# pla_xc9536.net
KiCad netlist of a schematic drawn in EAGLE
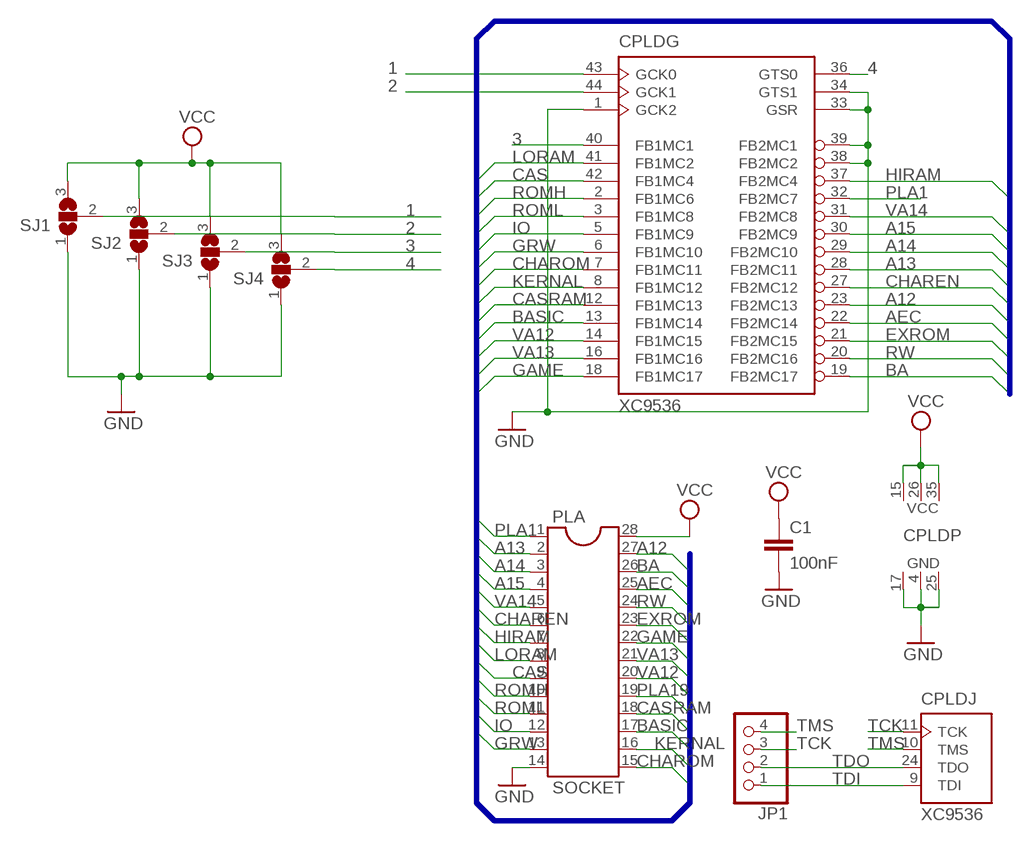
[diagram p0: schematic, sheet 1]

(export (version "E")
  (design (tool "Eeschema 10.0.6"))
  (components
    (comp (ref "C1")
      (value "100nF")
      (footprint "eagle-import:C1206K")
      (libsource (lib "eagle-import") (part "C-EUC1206K"))
    )
    (comp (ref "CPLD")
      (value "XC9536")
      (footprint "eagle-import:VQ44")
      (libsource (lib "eagle-import") (part "XC9536-44VQ44"))
    )
    (comp (ref "JP1")
      (value "PINHD-1X4")
      (footprint "eagle-import:1X04")
      (libsource (lib "eagle-import") (part "PINHD-1X4"))
    )
    (comp (ref "PLA")
      (value "SOCKET")
      (footprint "eagle-import:DIL28-6-ROUND")
      (libsource (lib "eagle-import") (part "DIL28"))
    )
    (comp (ref "SJ1")
      (value "SJ2W")
      (footprint "eagle-import:SJ_2")
      (libsource (lib "eagle-import") (part "SJ2W"))
    )
    (comp (ref "SJ2")
      (value "SJ2W")
      (footprint "eagle-import:SJ_2")
      (libsource (lib "eagle-import") (part "SJ2W"))
    )
    (comp (ref "SJ3")
      (value "SJ2W")
      (footprint "eagle-import:SJ_2")
      (libsource (lib "eagle-import") (part "SJ2W"))
    )
    (comp (ref "SJ4")
      (value "SJ2W")
      (footprint "eagle-import:SJ_2")
      (libsource (lib "eagle-import") (part "SJ2W"))
    )
  )
  (nets
    (net (code "1") (name "/1") (class "Default")
      (node (ref "CPLD") (pin "43") (pinfunction "GCK0_43") (pintype "input"))
      (node (ref "SJ1") (pin "2") (pinfunction "2_2") (pintype "passive"))
    )
    (net (code "2") (name "/2") (class "Default")
      (node (ref "CPLD") (pin "44") (pinfunction "GCK1_44") (pintype "input"))
      (node (ref "SJ2") (pin "2") (pinfunction "2_2") (pintype "passive"))
    )
    (net (code "3") (name "/3") (class "Default")
      (node (ref "CPLD") (pin "40") (pinfunction "FB1MC1_40") (pintype "bidirectional"))
      (node (ref "SJ3") (pin "2") (pinfunction "2_2") (pintype "passive"))
    )
    (net (code "4") (name "/4") (class "Default")
      (node (ref "CPLD") (pin "36") (pinfunction "GTS0_36") (pintype "input"))
      (node (ref "SJ4") (pin "2") (pinfunction "2_2") (pintype "passive"))
    )
    (net (code "5") (name "/A12") (class "Default")
      (node (ref "CPLD") (pin "23") (pinfunction "FB2MC13_23") (pintype "bidirectional"))
      (node (ref "PLA") (pin "27") (pinfunction "27_27") (pintype "passive"))
    )
    (net (code "6") (name "/A13") (class "Default")
      (node (ref "CPLD") (pin "28") (pinfunction "FB2MC11_28") (pintype "bidirectional"))
      (node (ref "PLA") (pin "2") (pinfunction "2_2") (pintype "passive"))
    )
    (net (code "7") (name "/A14") (class "Default")
      (node (ref "CPLD") (pin "29") (pinfunction "FB2MC10_29") (pintype "bidirectional"))
      (node (ref "PLA") (pin "3") (pinfunction "3_3") (pintype "passive"))
    )
    (net (code "8") (name "/A15") (class "Default")
      (node (ref "CPLD") (pin "30") (pinfunction "FB2MC9_30") (pintype "bidirectional"))
      (node (ref "PLA") (pin "4") (pinfunction "4_4") (pintype "passive"))
    )
    (net (code "9") (name "/AEC") (class "Default")
      (node (ref "CPLD") (pin "22") (pinfunction "FB2MC14_22") (pintype "bidirectional"))
      (node (ref "PLA") (pin "25") (pinfunction "25_25") (pintype "passive"))
    )
    (net (code "10") (name "/BA") (class "Default")
      (node (ref "CPLD") (pin "19") (pinfunction "FB2MC17_19") (pintype "bidirectional"))
      (node (ref "PLA") (pin "26") (pinfunction "26_26") (pintype "passive"))
    )
    (net (code "11") (name "/BASIC") (class "Default")
      (node (ref "CPLD") (pin "13") (pinfunction "FB1MC14_13") (pintype "bidirectional"))
      (node (ref "PLA") (pin "17") (pinfunction "17_17") (pintype "passive"))
    )
    (net (code "12") (name "/CAS") (class "Default")
      (node (ref "CPLD") (pin "42") (pinfunction "FB1MC4_42") (pintype "bidirectional"))
      (node (ref "PLA") (pin "9") (pinfunction "9_9") (pintype "passive"))
    )
    (net (code "13") (name "/CASRAM") (class "Default")
      (node (ref "CPLD") (pin "12") (pinfunction "FB1MC13_12") (pintype "bidirectional"))
      (node (ref "PLA") (pin "18") (pinfunction "18_18") (pintype "passive"))
    )
    (net (code "14") (name "/CHAREN") (class "Default")
      (node (ref "CPLD") (pin "27") (pinfunction "FB2MC12_27") (pintype "bidirectional"))
      (node (ref "PLA") (pin "6") (pinfunction "6_6") (pintype "passive"))
    )
    (net (code "15") (name "/CHAROM") (class "Default")
      (node (ref "CPLD") (pin "7") (pinfunction "FB1MC11_7") (pintype "bidirectional"))
      (node (ref "PLA") (pin "15") (pinfunction "15_15") (pintype "passive"))
    )
    (net (code "16") (name "/EXROM") (class "Default")
      (node (ref "CPLD") (pin "21") (pinfunction "FB2MC15_21") (pintype "bidirectional"))
      (node (ref "PLA") (pin "23") (pinfunction "23_23") (pintype "passive"))
    )
    (net (code "17") (name "/GAME") (class "Default")
      (node (ref "CPLD") (pin "18") (pinfunction "FB1MC17_18") (pintype "bidirectional"))
      (node (ref "PLA") (pin "22") (pinfunction "22_22") (pintype "passive"))
    )
    (net (code "18") (name "/GRW") (class "Default")
      (node (ref "CPLD") (pin "6") (pinfunction "FB1MC10_6") (pintype "bidirectional"))
      (node (ref "PLA") (pin "13") (pinfunction "13_13") (pintype "passive"))
    )
    (net (code "19") (name "/HIRAM") (class "Default")
      (node (ref "CPLD") (pin "37") (pinfunction "FB2MC4_37") (pintype "bidirectional"))
      (node (ref "PLA") (pin "7") (pinfunction "7_7") (pintype "passive"))
    )
    (net (code "20") (name "/IO") (class "Default")
      (node (ref "CPLD") (pin "5") (pinfunction "FB1MC9_5") (pintype "bidirectional"))
      (node (ref "PLA") (pin "12") (pinfunction "12_12") (pintype "passive"))
    )
    (net (code "21") (name "/KERNAL") (class "Default")
      (node (ref "CPLD") (pin "8") (pinfunction "FB1MC12_8") (pintype "bidirectional"))
      (node (ref "PLA") (pin "16") (pinfunction "16_16") (pintype "passive"))
    )
    (net (code "22") (name "/LORAM") (class "Default")
      (node (ref "CPLD") (pin "41") (pinfunction "FB1MC2_41") (pintype "bidirectional"))
      (node (ref "PLA") (pin "8") (pinfunction "8_8") (pintype "passive"))
    )
    (net (code "23") (name "/PLA1") (class "Default")
      (node (ref "CPLD") (pin "32") (pinfunction "FB2MC7_32") (pintype "bidirectional"))
      (node (ref "PLA") (pin "1") (pinfunction "1_1") (pintype "passive"))
    )
    (net (code "24") (name "/PLA19") (class "Default")
      (node (ref "PLA") (pin "19") (pinfunction "19_19") (pintype "passive"))
    )
    (net (code "25") (name "/ROMH") (class "Default")
      (node (ref "CPLD") (pin "2") (pinfunction "FB1MC6_2") (pintype "bidirectional"))
      (node (ref "PLA") (pin "10") (pinfunction "10_10") (pintype "passive"))
    )
    (net (code "26") (name "/ROML") (class "Default")
      (node (ref "CPLD") (pin "3") (pinfunction "FB1MC8_3") (pintype "bidirectional"))
      (node (ref "PLA") (pin "11") (pinfunction "11_11") (pintype "passive"))
    )
    (net (code "27") (name "/RW") (class "Default")
      (node (ref "CPLD") (pin "20") (pinfunction "FB2MC16_20") (pintype "bidirectional"))
      (node (ref "PLA") (pin "24") (pinfunction "24_24") (pintype "passive"))
    )
    (net (code "28") (name "/TCK") (class "Default")
      (node (ref "CPLD") (pin "11") (pinfunction "TCK_11") (pintype "input"))
      (node (ref "JP1") (pin "3") (pinfunction "3_3") (pintype "passive"))
    )
    (net (code "29") (name "/TDI") (class "Default")
      (node (ref "CPLD") (pin "9") (pinfunction "TDI_9") (pintype "input"))
      (node (ref "JP1") (pin "1") (pinfunction "1_1") (pintype "passive"))
    )
    (net (code "30") (name "/TDO") (class "Default")
      (node (ref "CPLD") (pin "24") (pinfunction "TDO_24") (pintype "output"))
      (node (ref "JP1") (pin "2") (pinfunction "2_2") (pintype "passive"))
    )
    (net (code "31") (name "/TMS") (class "Default")
      (node (ref "CPLD") (pin "10") (pinfunction "TMS_10") (pintype "input"))
      (node (ref "JP1") (pin "4") (pinfunction "4_4") (pintype "passive"))
    )
    (net (code "32") (name "/VA12") (class "Default")
      (node (ref "CPLD") (pin "14") (pinfunction "FB1MC15_14") (pintype "bidirectional"))
      (node (ref "PLA") (pin "20") (pinfunction "20_20") (pintype "passive"))
    )
    (net (code "33") (name "/VA13") (class "Default")
      (node (ref "CPLD") (pin "16") (pinfunction "FB1MC16_16") (pintype "bidirectional"))
      (node (ref "PLA") (pin "21") (pinfunction "21_21") (pintype "passive"))
    )
    (net (code "34") (name "/VA14") (class "Default")
      (node (ref "CPLD") (pin "31") (pinfunction "FB2MC8_31") (pintype "bidirectional"))
      (node (ref "PLA") (pin "5") (pinfunction "5_5") (pintype "passive"))
    )
    (net (code "35") (name "GND") (class "Default")
      (node (ref "C1") (pin "2") (pinfunction "2_2") (pintype "passive"))
      (node (ref "CPLD") (pin "1") (pinfunction "GCK2_1") (pintype "input"))
      (node (ref "CPLD") (pin "17") (pinfunction "GND_17") (pintype "power_in"))
      (node (ref "CPLD") (pin "25") (pinfunction "GND_25") (pintype "power_in"))
      (node (ref "CPLD") (pin "33") (pinfunction "GSR_33") (pintype "input"))
      (node (ref "CPLD") (pin "34") (pinfunction "GTS1_34") (pintype "input"))
      (node (ref "CPLD") (pin "38") (pinfunction "FB2MC2_38") (pintype "bidirectional"))
      (node (ref "CPLD") (pin "39") (pinfunction "FB2MC1_39") (pintype "bidirectional"))
      (node (ref "CPLD") (pin "4") (pinfunction "GND_4") (pintype "power_in"))
      (node (ref "PLA") (pin "14") (pinfunction "14_14") (pintype "passive"))
      (node (ref "SJ1") (pin "1") (pinfunction "1_1") (pintype "passive"))
      (node (ref "SJ2") (pin "1") (pinfunction "1_1") (pintype "passive"))
      (node (ref "SJ3") (pin "1") (pinfunction "1_1") (pintype "passive"))
      (node (ref "SJ4") (pin "1") (pinfunction "1_1") (pintype "passive"))
    )
    (net (code "36") (name "VCC") (class "Default")
      (node (ref "C1") (pin "1") (pinfunction "1_1") (pintype "passive"))
      (node (ref "CPLD") (pin "15") (pinfunction "VCC_15") (pintype "power_in"))
      (node (ref "CPLD") (pin "26") (pinfunction "VCC_26") (pintype "power_in"))
      (node (ref "CPLD") (pin "35") (pinfunction "VCC_35") (pintype "power_in"))
      (node (ref "PLA") (pin "28") (pinfunction "28_28") (pintype "passive"))
      (node (ref "SJ1") (pin "3") (pinfunction "3_3") (pintype "passive"))
      (node (ref "SJ2") (pin "3") (pinfunction "3_3") (pintype "passive"))
      (node (ref "SJ3") (pin "3") (pinfunction "3_3") (pintype "passive"))
      (node (ref "SJ4") (pin "3") (pinfunction "3_3") (pintype "passive"))
    )
  )
)
